# 03-PeripheralPart-V2_4.net
KiCad netlist of a schematic drawn in Altium Designer
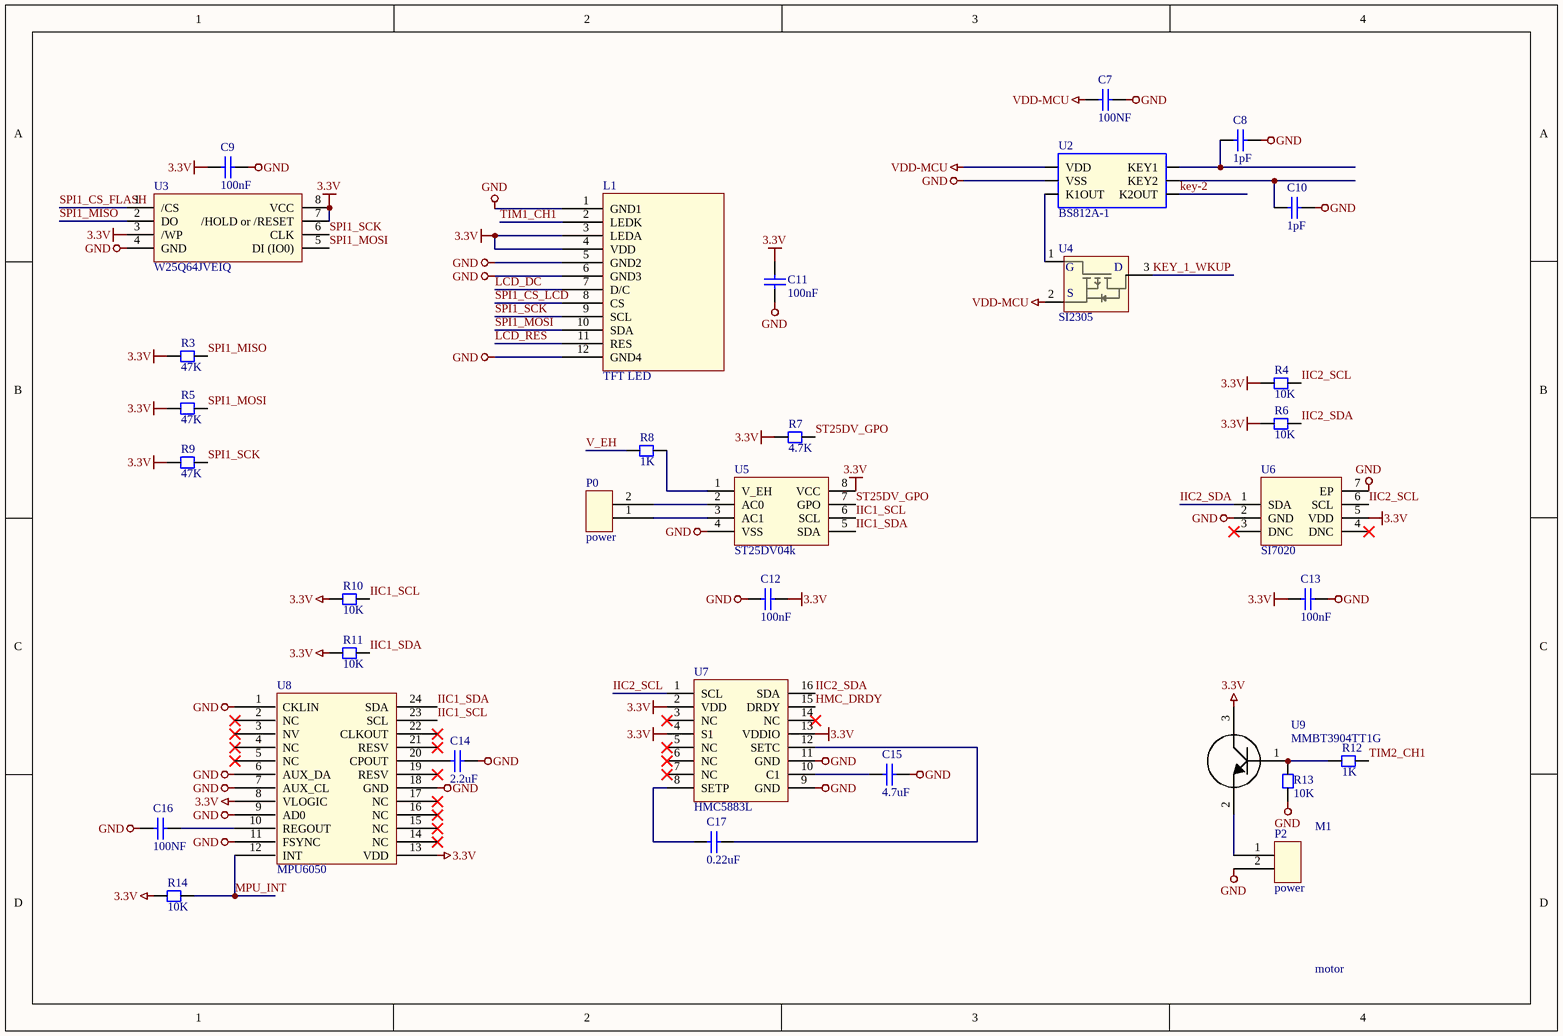
[diagram p0: 03-PeripheralPart-V2.4.SchDoc]

(export (version "E")
  (design (tool "Eeschema 10.0.6"))
  (components
    (comp (ref "C7")
      (value "100NF")
      (footprint "CC1005-0402")
      (description "贴片电容")
      (libsource (lib "tianxiaohua_Schlib") (part "Chip capacitor"))
    )
    (comp (ref "C8")
      (value "1pF")
      (footprint "CC1005-0402")
      (description "贴片电容")
      (libsource (lib "tianxiaohua_Schlib") (part "Chip capacitor"))
    )
    (comp (ref "C9")
      (value "100nF")
      (footprint "CC1005-0402")
      (description "贴片电容")
      (libsource (lib "tianxiaohua_Schlib") (part "Chip capacitor"))
    )
    (comp (ref "C10")
      (value "1pF")
      (footprint "CC1005-0402")
      (description "贴片电容")
      (libsource (lib "tianxiaohua_Schlib") (part "Chip capacitor"))
    )
    (comp (ref "C11")
      (value "100nF")
      (footprint "CC1005-0402")
      (description "贴片电容")
      (libsource (lib "tianxiaohua_Schlib") (part "Chip capacitor"))
    )
    (comp (ref "C12")
      (value "100nF")
      (footprint "CC1005-0402")
      (description "贴片电容")
      (libsource (lib "tianxiaohua_Schlib") (part "Chip capacitor"))
    )
    (comp (ref "C13")
      (value "100nF")
      (footprint "CC1005-0402")
      (description "贴片电容")
      (libsource (lib "tianxiaohua_Schlib") (part "Chip capacitor"))
    )
    (comp (ref "C14")
      (value "2.2uF")
      (footprint "CC1005-0402")
      (description "贴片电容")
      (libsource (lib "tianxiaohua_Schlib") (part "Chip capacitor"))
    )
    (comp (ref "C15")
      (value "4.7uF")
      (footprint "CC1005-0402")
      (description "贴片电容")
      (libsource (lib "tianxiaohua_Schlib") (part "Chip capacitor"))
    )
    (comp (ref "C16")
      (value "100NF")
      (footprint "CC1005-0402")
      (description "贴片电容")
      (libsource (lib "tianxiaohua_Schlib") (part "Chip capacitor"))
    )
    (comp (ref "C17")
      (value "0.22uF")
      (footprint "CC1005-0402")
      (description "贴片电容")
      (libsource (lib "tianxiaohua_Schlib") (part "Chip capacitor"))
    )
    (comp (ref "L1")
      (value "TFT LED")
      (footprint "LCD-1.3-(2)")
      (description "1.3寸显示屏幕")
      (libsource (lib "tianxiaohua_Schlib") (part "LCD-IPSscreen-1.3"))
    )
    (comp (ref "M1")
      (value "motor")
      (footprint "motor")
      (description "震动马达")
      (libsource (lib "tianxiaohua_Schlib") (part "motor"))
    )
    (comp (ref "P0") (value "power") (footprint "POWER2") (libsource (lib "") (part "power_1")))
    (comp (ref "P2")
      (value "power")
      (footprint "POWER-3.7V")
      (libsource (lib "tianxiaohua_Schlib") (part "power"))
    )
    (comp (ref "R3")
      (value "47K")
      (footprint "CR1005-0402")
      (description "贴片电阻")
      (libsource (lib "tianxiaohua_Schlib") (part "Chip resistor"))
    )
    (comp (ref "R4")
      (value "10K")
      (footprint "CR1005-0402")
      (description "贴片电阻")
      (libsource (lib "tianxiaohua_Schlib") (part "Chip resistor"))
    )
    (comp (ref "R5")
      (value "47K")
      (footprint "CR1005-0402")
      (description "贴片电阻")
      (libsource (lib "tianxiaohua_Schlib") (part "Chip resistor"))
    )
    (comp (ref "R6")
      (value "10K")
      (footprint "CR1005-0402")
      (description "贴片电阻")
      (libsource (lib "tianxiaohua_Schlib") (part "Chip resistor"))
    )
    (comp (ref "R7")
      (value "4.7K")
      (footprint "CR1005-0402")
      (description "贴片电阻")
      (libsource (lib "") (part "Chip resistor_2"))
    )
    (comp (ref "R8")
      (value "1K")
      (footprint "CR1005-0402")
      (description "贴片电阻")
      (libsource (lib "tianxiaohua_Schlib") (part "Chip resistor"))
    )
    (comp (ref "R9")
      (value "47K")
      (footprint "CR1005-0402")
      (description "贴片电阻")
      (libsource (lib "tianxiaohua_Schlib") (part "Chip resistor"))
    )
    (comp (ref "R10")
      (value "10K")
      (footprint "CR1005-0402")
      (description "贴片电阻")
      (libsource (lib "tianxiaohua_Schlib") (part "Chip resistor"))
    )
    (comp (ref "R11")
      (value "10K")
      (footprint "CR1005-0402")
      (description "贴片电阻")
      (libsource (lib "tianxiaohua_Schlib") (part "Chip resistor"))
    )
    (comp (ref "R12")
      (value "1K")
      (footprint "CR1005-0402")
      (description "贴片电阻")
      (libsource (lib "tianxiaohua_Schlib") (part "Chip resistor"))
    )
    (comp (ref "R13")
      (value "10K")
      (footprint "CR1005-0402")
      (description "贴片电阻")
      (libsource (lib "") (part "Chip resistor_1"))
    )
    (comp (ref "R14")
      (value "10K")
      (footprint "CR1005-0402")
      (description "贴片电阻")
      (libsource (lib "tianxiaohua_Schlib") (part "Chip resistor"))
    )
    (comp (ref "U2")
      (value "BS812A-1")
      (footprint "SOT23-6")
      (description "触摸按键 两路 SOP23-6封装极简电路")
      (libsource (lib "tianxiaohua_Schlib") (part "BS812A-1"))
    )
    (comp (ref "U3")
      (value "W25Q64JVEIQ")
      (footprint "WSON-8_L8.0-W6.10-P1.27-TL-EP")
      (description "FLASH")
      (libsource (lib "tianxiaohua_Schlib") (part "W25Q256JVEIQ"))
    )
    (comp (ref "U4")
      (value "SI2305")
      (footprint "SOT-23")
      (description "PMOS场效应MOS管 SOT-23")
      (libsource (lib "tianxiaohua_Schlib") (part "SI2305"))
    )
    (comp (ref "U5")
      (value "ST25DV04k")
      (footprint "UFDFPN8")
      (description "NFC芯片4K存储空间")
      (libsource (lib "tianxiaohua_Schlib") (part "ST25DV04k"))
    )
    (comp (ref "U6")
      (value "SI7020")
      (footprint "DFN-6")
      (description "温湿度传感器芯片")
      (libsource (lib "tianxiaohua_Schlib") (part "SI7020"))
    )
    (comp (ref "U7")
      (value "HMC5883L")
      (footprint "LPCC-16_L3.0-W3.0-P0.50-BL")
      (description "三轴罗盘")
      (libsource (lib "tianxiaohua_Schlib") (part "HMC5883L"))
    )
    (comp (ref "U8")
      (value "MPU6050")
      (footprint "QFN24 - duplicate")
      (description "陀螺仪")
      (libsource (lib "tianxiaohua_Schlib") (part "MPU6050"))
    )
    (comp (ref "U9")
      (value "MMBT3904TT1G")
      (footprint "SOT-416")
      (description "NPN 电流 - 集电极（Ic）（最大值）：200mA 电压 - 集射极击穿（最大值）：40V SOT-23-3")
      (libsource (lib "tianxiaohua_Schlib") (part "MMBT3904TT1G"))
    )
  )
  (nets
    (net (code "1") (name "/HMC_DRDY") (class "Default")
      (node (ref "U7") (pin "15") (pinfunction "DRDY_15") (pintype "passive"))
    )
    (net (code "2") (name "/IIC1_SCL") (class "Default")
      (node (ref "R10") (pin "1") (pinfunction "1_1") (pintype "passive"))
      (node (ref "U5") (pin "6") (pinfunction "SCL_6") (pintype "passive"))
      (node (ref "U8") (pin "23") (pinfunction "SCL_23") (pintype "passive"))
    )
    (net (code "3") (name "/IIC1_SDA") (class "Default")
      (node (ref "R11") (pin "1") (pinfunction "1_1") (pintype "passive"))
      (node (ref "U5") (pin "5") (pinfunction "SDA_5") (pintype "passive"))
      (node (ref "U8") (pin "24") (pinfunction "SDA_24") (pintype "passive"))
    )
    (net (code "4") (name "/IIC2_SCL") (class "Default")
      (node (ref "R4") (pin "1") (pinfunction "1_1") (pintype "passive"))
      (node (ref "U6") (pin "6") (pinfunction "SCL_6") (pintype "passive"))
      (node (ref "U7") (pin "1") (pinfunction "SCL_1") (pintype "passive"))
    )
    (net (code "5") (name "/IIC2_SDA") (class "Default")
      (node (ref "R6") (pin "1") (pinfunction "1_1") (pintype "passive"))
      (node (ref "U6") (pin "1") (pinfunction "SDA_1") (pintype "passive"))
      (node (ref "U7") (pin "16") (pinfunction "SDA_16") (pintype "passive"))
    )
    (net (code "6") (name "/KEY_1_WKUP") (class "Default")
      (node (ref "U4") (pin "3") (pinfunction "DRAIN_3") (pintype "passive"))
    )
    (net (code "7") (name "/LCD_DC") (class "Default")
      (node (ref "L1") (pin "7") (pinfunction "D/C_7") (pintype "passive"))
    )
    (net (code "8") (name "/LCD_RES") (class "Default")
      (node (ref "L1") (pin "11") (pinfunction "RES_11") (pintype "passive"))
    )
    (net (code "9") (name "/MPU_INT") (class "Default")
      (node (ref "R14") (pin "1") (pinfunction "1_1") (pintype "passive"))
      (node (ref "U8") (pin "12") (pinfunction "INT_12") (pintype "passive"))
    )
    (net (code "10") (name "/SPI1_CS_FLASH") (class "Default")
      (node (ref "U3") (pin "1") (pinfunction "/CS_1") (pintype "passive"))
    )
    (net (code "11") (name "/SPI1_CS_LCD") (class "Default")
      (node (ref "L1") (pin "8") (pinfunction "CS_8") (pintype "passive"))
    )
    (net (code "12") (name "/SPI1_MISO") (class "Default")
      (node (ref "R3") (pin "1") (pinfunction "1_1") (pintype "passive"))
      (node (ref "U3") (pin "2") (pinfunction "DO_2") (pintype "passive"))
    )
    (net (code "13") (name "/SPI1_MOSI") (class "Default")
      (node (ref "L1") (pin "10") (pinfunction "SDA_10") (pintype "passive"))
      (node (ref "R5") (pin "1") (pinfunction "1_1") (pintype "passive"))
      (node (ref "U3") (pin "5") (pinfunction "DI_(IO0)_5") (pintype "passive"))
    )
    (net (code "14") (name "/SPI1_SCK") (class "Default")
      (node (ref "L1") (pin "9") (pinfunction "SCL_9") (pintype "passive"))
      (node (ref "R9") (pin "1") (pinfunction "1_1") (pintype "passive"))
      (node (ref "U3") (pin "6") (pinfunction "CLK_6") (pintype "passive"))
    )
    (net (code "15") (name "/ST25DV_GPO") (class "Default")
      (node (ref "R7") (pin "2") (pinfunction "2_2") (pintype "passive"))
      (node (ref "U5") (pin "7") (pinfunction "GPO_7") (pintype "passive"))
    )
    (net (code "16") (name "/TIM1_CH1") (class "Default")
      (node (ref "L1") (pin "2") (pinfunction "LEDK_2") (pintype "passive"))
    )
    (net (code "17") (name "/TIM2_CH1") (class "Default")
      (node (ref "R12") (pin "1") (pinfunction "1_1") (pintype "passive"))
    )
    (net (code "18") (name "/V_EH") (class "Default")
      (node (ref "R8") (pin "2") (pinfunction "2_2") (pintype "passive"))
    )
    (net (code "19") (name "/key-2") (class "Default")
      (node (ref "U2") (pin "4") (pinfunction "K2OUT_4") (pintype "passive"))
    )
    (net (code "20") (name "3.3V") (class "Default")
      (node (ref "C11") (pin "1") (pinfunction "1_1") (pintype "passive"))
      (node (ref "C12") (pin "2") (pinfunction "2_2") (pintype "passive"))
      (node (ref "C13") (pin "1") (pinfunction "1_1") (pintype "passive"))
      (node (ref "C9") (pin "1") (pinfunction "1_1") (pintype "passive"))
      (node (ref "L1") (pin "3") (pinfunction "LEDA_3") (pintype "passive"))
      (node (ref "L1") (pin "4") (pinfunction "VDD_4") (pintype "passive"))
      (node (ref "R10") (pin "2") (pinfunction "2_2") (pintype "passive"))
      (node (ref "R11") (pin "2") (pinfunction "2_2") (pintype "passive"))
      (node (ref "R14") (pin "2") (pinfunction "2_2") (pintype "passive"))
      (node (ref "R3") (pin "2") (pinfunction "2_2") (pintype "passive"))
      (node (ref "R4") (pin "2") (pinfunction "2_2") (pintype "passive"))
      (node (ref "R5") (pin "2") (pinfunction "2_2") (pintype "passive"))
      (node (ref "R6") (pin "2") (pinfunction "2_2") (pintype "passive"))
      (node (ref "R7") (pin "1") (pinfunction "1_1") (pintype "passive"))
      (node (ref "R9") (pin "2") (pinfunction "2_2") (pintype "passive"))
      (node (ref "U3") (pin "3") (pinfunction "/WP_3") (pintype "passive"))
      (node (ref "U3") (pin "7") (pinfunction "/HOLD_or_/RESET_7") (pintype "passive"))
      (node (ref "U3") (pin "8") (pinfunction "VCC_8") (pintype "passive"))
      (node (ref "U5") (pin "8") (pinfunction "VCC_8") (pintype "passive"))
      (node (ref "U6") (pin "5") (pinfunction "VDD_5") (pintype "passive"))
      (node (ref "U7") (pin "13") (pinfunction "VDDIO_13") (pintype "passive"))
      (node (ref "U7") (pin "2") (pinfunction "VDD_2") (pintype "passive"))
      (node (ref "U7") (pin "4") (pinfunction "S1_4") (pintype "passive"))
      (node (ref "U8") (pin "13") (pinfunction "VDD_13") (pintype "passive"))
      (node (ref "U8") (pin "8") (pinfunction "VLOGIC_8") (pintype "passive"))
      (node (ref "U9") (pin "3") (pinfunction "3_3") (pintype "passive"))
    )
    (net (code "21") (name "GND") (class "Default")
      (node (ref "C10") (pin "2") (pinfunction "2_2") (pintype "passive"))
      (node (ref "C11") (pin "2") (pinfunction "2_2") (pintype "passive"))
      (node (ref "C12") (pin "1") (pinfunction "1_1") (pintype "passive"))
      (node (ref "C13") (pin "2") (pinfunction "2_2") (pintype "passive"))
      (node (ref "C14") (pin "2") (pinfunction "2_2") (pintype "passive"))
      (node (ref "C15") (pin "2") (pinfunction "2_2") (pintype "passive"))
      (node (ref "C16") (pin "1") (pinfunction "1_1") (pintype "passive"))
      (node (ref "C7") (pin "1") (pinfunction "1_1") (pintype "passive"))
      (node (ref "C8") (pin "2") (pinfunction "2_2") (pintype "passive"))
      (node (ref "C9") (pin "2") (pinfunction "2_2") (pintype "passive"))
      (node (ref "L1") (pin "1") (pinfunction "GND1_1") (pintype "passive"))
      (node (ref "L1") (pin "12") (pinfunction "GND4_12") (pintype "passive"))
      (node (ref "L1") (pin "5") (pinfunction "GND2_5") (pintype "passive"))
      (node (ref "L1") (pin "6") (pinfunction "GND3_6") (pintype "passive"))
      (node (ref "P2") (pin "2") (pinfunction "2_2") (pintype "passive"))
      (node (ref "R13") (pin "2") (pinfunction "2_2") (pintype "passive"))
      (node (ref "U2") (pin "2") (pinfunction "VSS_2") (pintype "passive"))
      (node (ref "U3") (pin "4") (pinfunction "GND_4") (pintype "passive"))
      (node (ref "U5") (pin "4") (pinfunction "VSS_4") (pintype "passive"))
      (node (ref "U6") (pin "2") (pinfunction "GND_2") (pintype "passive"))
      (node (ref "U6") (pin "7") (pinfunction "EP_7") (pintype "passive"))
      (node (ref "U7") (pin "11") (pinfunction "GND_11") (pintype "passive"))
      (node (ref "U7") (pin "9") (pinfunction "GND_9") (pintype "passive"))
      (node (ref "U8") (pin "1") (pinfunction "CKLIN_1") (pintype "passive"))
      (node (ref "U8") (pin "11") (pinfunction "FSYNC_11") (pintype "passive"))
      (node (ref "U8") (pin "18") (pinfunction "GND_18") (pintype "passive"))
      (node (ref "U8") (pin "6") (pinfunction "AUX_DA_6") (pintype "passive"))
      (node (ref "U8") (pin "7") (pinfunction "AUX_CL_7") (pintype "passive"))
      (node (ref "U8") (pin "9") (pinfunction "AD0_9") (pintype "passive"))
    )
    (net (code "22") (name "Net-(P2-Pad1)") (class "Default")
      (node (ref "P2") (pin "1") (pinfunction "1_1") (pintype "passive"))
      (node (ref "U9") (pin "2") (pinfunction "2_2") (pintype "passive"))
    )
    (net (code "23") (name "Net-(R12-Pad2)") (class "Default")
      (node (ref "R12") (pin "2") (pinfunction "2_2") (pintype "passive"))
      (node (ref "R13") (pin "1") (pinfunction "1_1") (pintype "passive"))
      (node (ref "U9") (pin "1") (pinfunction "1_1") (pintype "passive"))
    )
    (net (code "24") (name "Net-(U2-K1OUT)") (class "Default")
      (node (ref "U2") (pin "3") (pinfunction "K1OUT_3") (pintype "passive"))
      (node (ref "U4") (pin "1") (pinfunction "GATE_1") (pintype "passive"))
    )
    (net (code "25") (name "Net-(U2-KEY1)") (class "Default")
      (node (ref "C8") (pin "1") (pinfunction "1_1") (pintype "passive"))
      (node (ref "U2") (pin "6") (pinfunction "KEY1_6") (pintype "passive"))
    )
    (net (code "26") (name "Net-(U2-KEY2)") (class "Default")
      (node (ref "C10") (pin "1") (pinfunction "1_1") (pintype "passive"))
      (node (ref "U2") (pin "5") (pinfunction "KEY2_5") (pintype "passive"))
    )
    (net (code "27") (name "Net-(U5-AC0)") (class "Default")
      (node (ref "P0") (pin "2") (pinfunction "2_2") (pintype "passive"))
      (node (ref "U5") (pin "2") (pinfunction "AC0_2") (pintype "passive"))
    )
    (net (code "28") (name "Net-(U5-AC1)") (class "Default")
      (node (ref "P0") (pin "1") (pinfunction "1_1") (pintype "passive"))
      (node (ref "U5") (pin "3") (pinfunction "AC1_3") (pintype "passive"))
    )
    (net (code "29") (name "Net-(U5-V_EH)") (class "Default")
      (node (ref "R8") (pin "1") (pinfunction "1_1") (pintype "passive"))
      (node (ref "U5") (pin "1") (pinfunction "V_EH_1") (pintype "passive"))
    )
    (net (code "30") (name "Net-(U7-C1)") (class "Default")
      (node (ref "C15") (pin "1") (pinfunction "1_1") (pintype "passive"))
      (node (ref "U7") (pin "10") (pinfunction "C1_10") (pintype "passive"))
    )
    (net (code "31") (name "Net-(U7-SETC)") (class "Default")
      (node (ref "C17") (pin "2") (pinfunction "2_2") (pintype "passive"))
      (node (ref "U7") (pin "12") (pinfunction "SETC_12") (pintype "passive"))
    )
    (net (code "32") (name "Net-(U7-SETP)") (class "Default")
      (node (ref "C17") (pin "1") (pinfunction "1_1") (pintype "passive"))
      (node (ref "U7") (pin "8") (pinfunction "SETP_8") (pintype "passive"))
    )
    (net (code "33") (name "Net-(U8-CPOUT)") (class "Default")
      (node (ref "C14") (pin "1") (pinfunction "1_1") (pintype "passive"))
      (node (ref "U8") (pin "20") (pinfunction "CPOUT_20") (pintype "passive"))
    )
    (net (code "34") (name "Net-(U8-REGOUT)") (class "Default")
      (node (ref "C16") (pin "2") (pinfunction "2_2") (pintype "passive"))
      (node (ref "U8") (pin "10") (pinfunction "REGOUT_10") (pintype "passive"))
    )
    (net (code "35") (name "VDD-MCU") (class "Default")
      (node (ref "C7") (pin "2") (pinfunction "2_2") (pintype "passive"))
      (node (ref "U2") (pin "1") (pinfunction "VDD_1") (pintype "passive"))
      (node (ref "U4") (pin "2") (pinfunction "SOURCE_2") (pintype "passive"))
    )
    (net (code "36") (name "unconnected-(U6-DNC-Pad3)") (class "Default")
      (node (ref "U6") (pin "3") (pinfunction "DNC_3") (pintype "passive+no_connect"))
    )
    (net (code "37") (name "unconnected-(U6-DNC-Pad4)") (class "Default")
      (node (ref "U6") (pin "4") (pinfunction "DNC_4") (pintype "passive+no_connect"))
    )
    (net (code "38") (name "unconnected-(U7-NC-Pad3)") (class "Default")
      (node (ref "U7") (pin "3") (pinfunction "NC_3") (pintype "passive+no_connect"))
    )
    (net (code "39") (name "unconnected-(U7-NC-Pad5)") (class "Default")
      (node (ref "U7") (pin "5") (pinfunction "NC_5") (pintype "passive+no_connect"))
    )
    (net (code "40") (name "unconnected-(U7-NC-Pad6)") (class "Default")
      (node (ref "U7") (pin "6") (pinfunction "NC_6") (pintype "passive+no_connect"))
    )
    (net (code "41") (name "unconnected-(U7-NC-Pad7)") (class "Default")
      (node (ref "U7") (pin "7") (pinfunction "NC_7") (pintype "passive+no_connect"))
    )
    (net (code "42") (name "unconnected-(U7-NC-Pad14)") (class "Default")
      (node (ref "U7") (pin "14") (pinfunction "NC_14") (pintype "passive+no_connect"))
    )
    (net (code "43") (name "unconnected-(U8-CLKOUT-Pad22)") (class "Default")
      (node (ref "U8") (pin "22") (pinfunction "CLKOUT_22") (pintype "passive+no_connect"))
    )
    (net (code "44") (name "unconnected-(U8-NC-Pad2)") (class "Default")
      (node (ref "U8") (pin "2") (pinfunction "NC_2") (pintype "passive+no_connect"))
    )
    (net (code "45") (name "unconnected-(U8-NC-Pad4)") (class "Default")
      (node (ref "U8") (pin "4") (pinfunction "NC_4") (pintype "passive+no_connect"))
    )
    (net (code "46") (name "unconnected-(U8-NC-Pad5)") (class "Default")
      (node (ref "U8") (pin "5") (pinfunction "NC_5") (pintype "passive+no_connect"))
    )
    (net (code "47") (name "unconnected-(U8-NC-Pad14)") (class "Default")
      (node (ref "U8") (pin "14") (pinfunction "NC_14") (pintype "passive+no_connect"))
    )
    (net (code "48") (name "unconnected-(U8-NC-Pad15)") (class "Default")
      (node (ref "U8") (pin "15") (pinfunction "NC_15") (pintype "passive+no_connect"))
    )
    (net (code "49") (name "unconnected-(U8-NC-Pad16)") (class "Default")
      (node (ref "U8") (pin "16") (pinfunction "NC_16") (pintype "passive+no_connect"))
    )
    (net (code "50") (name "unconnected-(U8-NC-Pad17)") (class "Default")
      (node (ref "U8") (pin "17") (pinfunction "NC_17") (pintype "passive+no_connect"))
    )
    (net (code "51") (name "unconnected-(U8-NV-Pad3)") (class "Default")
      (node (ref "U8") (pin "3") (pinfunction "NV_3") (pintype "passive+no_connect"))
    )
    (net (code "52") (name "unconnected-(U8-RESV-Pad19)") (class "Default")
      (node (ref "U8") (pin "19") (pinfunction "RESV_19") (pintype "passive+no_connect"))
    )
    (net (code "53") (name "unconnected-(U8-RESV-Pad21)") (class "Default")
      (node (ref "U8") (pin "21") (pinfunction "RESV_21") (pintype "passive+no_connect"))
    )
  )
)
